# mc_run.net
KiCad netlist of a schematic drawn in EAGLE
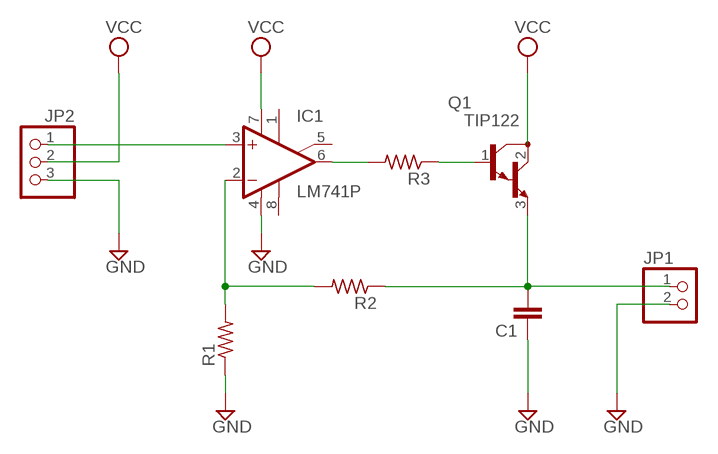
[diagram p0: schematic, sheet 1]

(export (version "E")
  (design (tool "Eeschema 10.0.6"))
  (components
    (comp (ref "C1")
      (value "C7.5/3")
      (footprint "eagle-import:C7.5B3")
      (libsource (lib "eagle-import") (part "C7.5/3"))
    )
    (comp (ref "IC1")
      (value "LM741P")
      (footprint "eagle-import:DIL08")
      (libsource (lib "eagle-import") (part "741PLM"))
    )
    (comp (ref "JP1")
      (value "PINHD-1X2")
      (footprint "eagle-import:1X02")
      (libsource (lib "eagle-import") (part "PINHD-1X2"))
    )
    (comp (ref "JP2")
      (value "PINHD-1X3")
      (footprint "eagle-import:1X03")
      (libsource (lib "eagle-import") (part "PINHD-1X3"))
    )
    (comp (ref "Q1")
      (value "TIP122")
      (footprint "eagle-import:TO220")
      (libsource (lib "eagle-import") (part "TIP122"))
    )
    (comp (ref "R1")
      (value "R-US_0411/15")
      (footprint "eagle-import:0411_15")
      (libsource (lib "eagle-import") (part "R-US_0411/15"))
    )
    (comp (ref "R2")
      (value "R-US_0411/15")
      (footprint "eagle-import:0411_15")
      (libsource (lib "eagle-import") (part "R-US_0411/15"))
    )
    (comp (ref "R3")
      (value "R-US_0411/15")
      (footprint "eagle-import:0411_15")
      (libsource (lib "eagle-import") (part "R-US_0411/15"))
    )
  )
  (nets
    (net (code "1") (name "GND") (class "Default")
      (node (ref "C1") (pin "1") (pinfunction "1_1") (pintype "passive"))
      (node (ref "IC1") (pin "4") (pinfunction "V-_4") (pintype "power_in"))
      (node (ref "JP1") (pin "2") (pinfunction "2_2") (pintype "passive"))
      (node (ref "JP2") (pin "3") (pinfunction "3_3") (pintype "passive"))
      (node (ref "R1") (pin "1") (pinfunction "1_1") (pintype "passive"))
    )
    (net (code "2") (name "Net-(IC1-+IN)") (class "Default")
      (node (ref "IC1") (pin "3") (pinfunction "+IN_3") (pintype "input"))
      (node (ref "JP2") (pin "1") (pinfunction "1_1") (pintype "passive"))
    )
    (net (code "3") (name "Net-(IC1--IN)") (class "Default")
      (node (ref "IC1") (pin "2") (pinfunction "-IN_2") (pintype "input"))
      (node (ref "R1") (pin "2") (pinfunction "2_2") (pintype "passive"))
      (node (ref "R2") (pin "2") (pinfunction "2_2") (pintype "passive"))
    )
    (net (code "4") (name "Net-(IC1-OUT)") (class "Default")
      (node (ref "IC1") (pin "6") (pinfunction "OUT_6") (pintype "output"))
      (node (ref "R3") (pin "2") (pinfunction "2_2") (pintype "passive"))
    )
    (net (code "5") (name "Net-(Q1-B)") (class "Default")
      (node (ref "Q1") (pin "1") (pinfunction "B_1") (pintype "passive"))
      (node (ref "R3") (pin "1") (pinfunction "1_1") (pintype "passive"))
    )
    (net (code "6") (name "Net-(Q1-E)") (class "Default")
      (node (ref "C1") (pin "2") (pinfunction "2_2") (pintype "passive"))
      (node (ref "JP1") (pin "1") (pinfunction "1_1") (pintype "passive"))
      (node (ref "Q1") (pin "3") (pinfunction "E_3") (pintype "passive"))
      (node (ref "R2") (pin "1") (pinfunction "1_1") (pintype "passive"))
    )
    (net (code "7") (name "VCC") (class "Default")
      (node (ref "IC1") (pin "7") (pinfunction "V+_7") (pintype "power_in"))
      (node (ref "JP2") (pin "2") (pinfunction "2_2") (pintype "passive"))
      (node (ref "Q1") (pin "2") (pinfunction "C_2") (pintype "passive"))
    )
    (net (code "8") (name "unconnected-(IC1-ON1-Pad1)") (class "Default")
      (node (ref "IC1") (pin "1") (pinfunction "ON1_1") (pintype "passive"))
    )
    (net (code "9") (name "unconnected-(IC1-ON2-Pad5)") (class "Default")
      (node (ref "IC1") (pin "5") (pinfunction "ON2_5") (pintype "passive"))
    )
    (net (code "10") (name "unconnected-(IC1-OPT-Pad8)") (class "Default")
      (node (ref "IC1") (pin "8") (pinfunction "OPT_8") (pintype "passive"))
    )
  )
)
